# test1.net
KiCad netlist of a schematic drawn in EAGLE
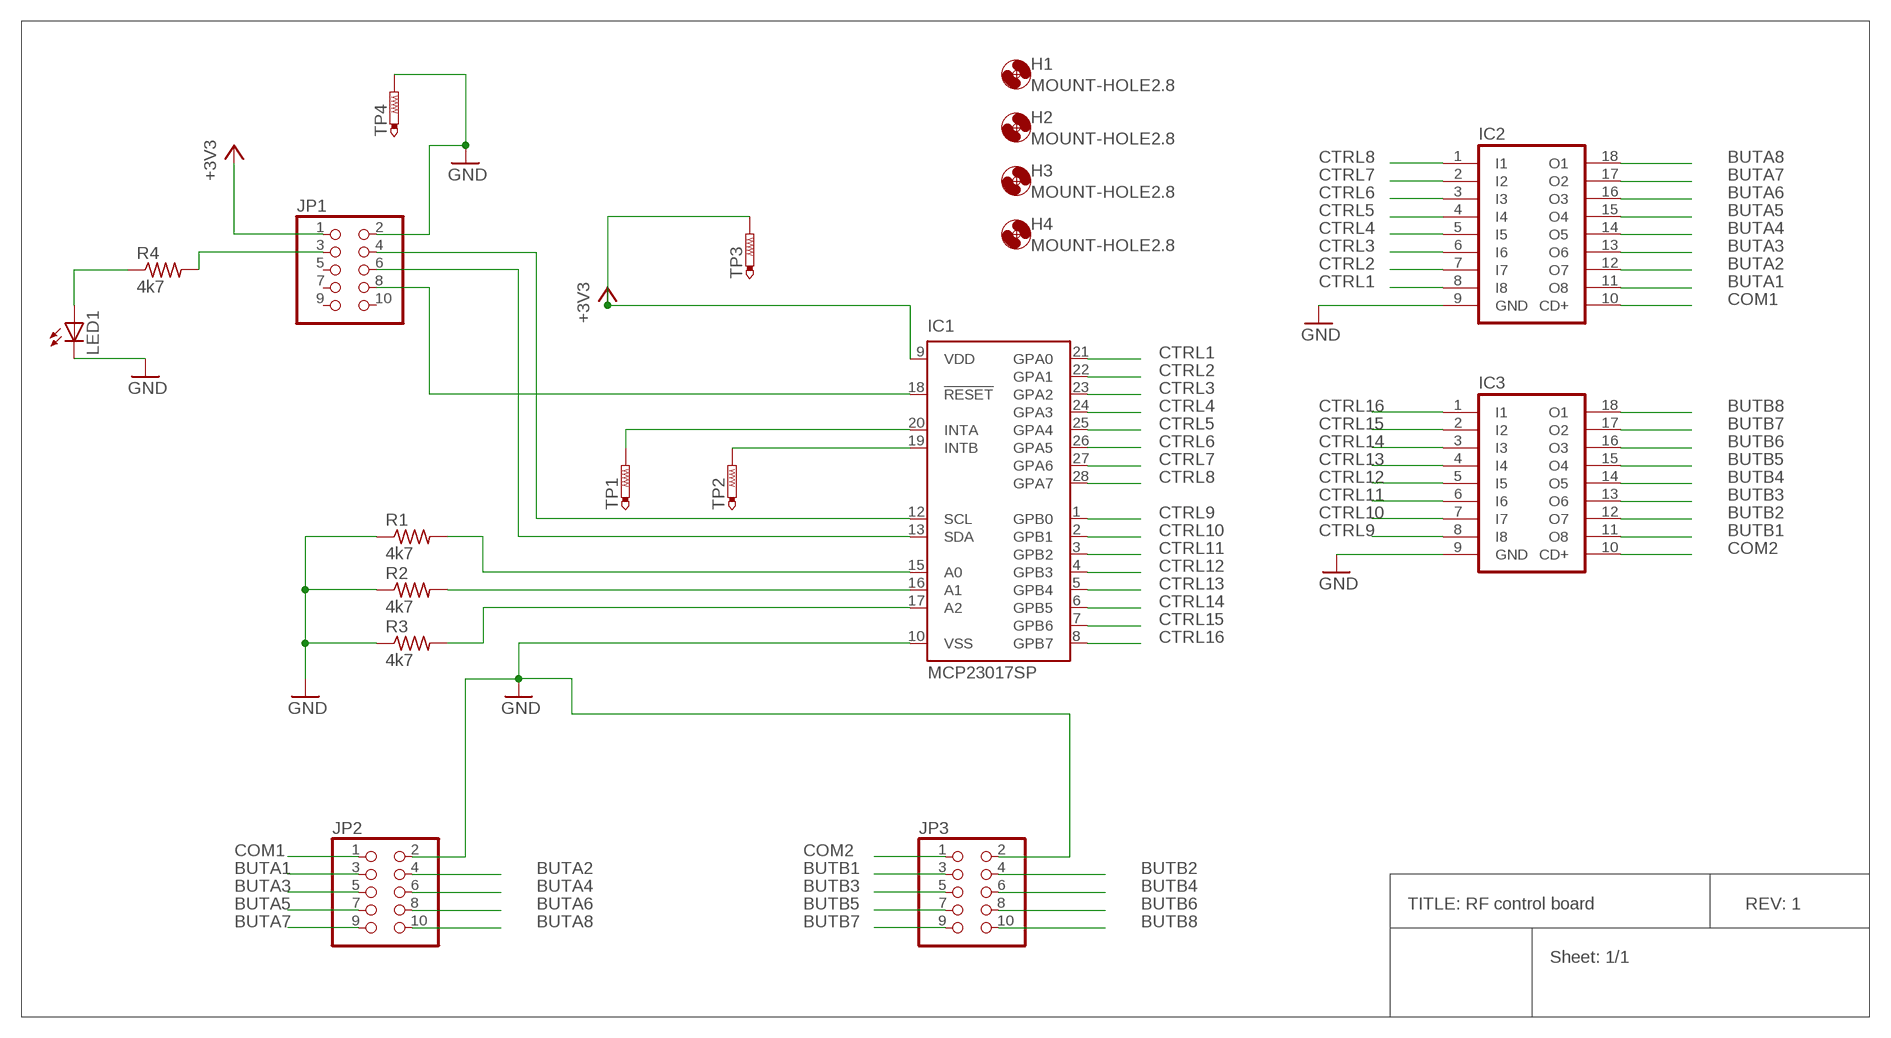
[diagram p0: schematic, sheet 1]

(export (version "E")
  (design (tool "Eeschema 10.0.6"))
  (components
    (comp (ref "H1")
      (value "MOUNT-HOLE2.8")
      (footprint "eagle-import:2,8")
      (libsource (lib "eagle-import") (part "MOUNT-HOLE2.8"))
    )
    (comp (ref "H2")
      (value "MOUNT-HOLE2.8")
      (footprint "eagle-import:2,8")
      (libsource (lib "eagle-import") (part "MOUNT-HOLE2.8"))
    )
    (comp (ref "H3")
      (value "MOUNT-HOLE2.8")
      (footprint "eagle-import:2,8")
      (libsource (lib "eagle-import") (part "MOUNT-HOLE2.8"))
    )
    (comp (ref "H4")
      (value "MOUNT-HOLE2.8")
      (footprint "eagle-import:2,8")
      (libsource (lib "eagle-import") (part "MOUNT-HOLE2.8"))
    )
    (comp (ref "IC1")
      (value "MCP23017SP")
      (footprint "eagle-import:DIL28-3")
      (libsource (lib "eagle-import") (part "MCP23017SP"))
    )
    (comp (ref "IC2")
      (value "ULN2803A")
      (footprint "eagle-import:DIL18")
      (libsource (lib "eagle-import") (part "ULN2803A"))
    )
    (comp (ref "IC3")
      (value "ULN2803A")
      (footprint "eagle-import:DIL18")
      (libsource (lib "eagle-import") (part "ULN2803A"))
    )
    (comp (ref "JP1")
      (value "PINHD-2X5")
      (footprint "eagle-import:2X05")
      (libsource (lib "eagle-import") (part "PINHD-2X5"))
    )
    (comp (ref "JP2")
      (value "PINHD-2X5")
      (footprint "eagle-import:2X05")
      (libsource (lib "eagle-import") (part "PINHD-2X5"))
    )
    (comp (ref "JP3")
      (value "PINHD-2X5")
      (footprint "eagle-import:2X05")
      (libsource (lib "eagle-import") (part "PINHD-2X5"))
    )
    (comp (ref "LED1")
      (value "LED5MM")
      (footprint "eagle-import:LED5MM")
      (libsource (lib "eagle-import") (part "LED5MM"))
    )
    (comp (ref "R1")
      (value "4k7")
      (footprint "eagle-import:0207_2V")
      (libsource (lib "eagle-import") (part "R-US_0207/2V"))
    )
    (comp (ref "R2")
      (value "4k7")
      (footprint "eagle-import:0207_2V")
      (libsource (lib "eagle-import") (part "R-US_0207/2V"))
    )
    (comp (ref "R3")
      (value "4k7")
      (footprint "eagle-import:0207_2V")
      (libsource (lib "eagle-import") (part "R-US_0207/2V"))
    )
    (comp (ref "R4")
      (value "4k7")
      (footprint "eagle-import:0207_2V")
      (libsource (lib "eagle-import") (part "R-US_0207/2V"))
    )
    (comp (ref "TP1")
      (value "PTR1B2,54")
      (footprint "eagle-import:B2,54")
      (libsource (lib "eagle-import") (part "PTR1B2,54"))
    )
    (comp (ref "TP2")
      (value "PTR1B2,54")
      (footprint "eagle-import:B2,54")
      (libsource (lib "eagle-import") (part "PTR1B2,54"))
    )
    (comp (ref "TP3")
      (value "PTR1B2,54")
      (footprint "eagle-import:B2,54")
      (libsource (lib "eagle-import") (part "PTR1B2,54"))
    )
    (comp (ref "TP4")
      (value "PTR1B2,54")
      (footprint "eagle-import:B2,54")
      (libsource (lib "eagle-import") (part "PTR1B2,54"))
    )
  )
  (nets
    (net (code "1") (name "+3V3") (class "Default")
      (node (ref "IC1") (pin "9") (pinfunction "VDD_9") (pintype "power_in"))
      (node (ref "JP1") (pin "1") (pinfunction "1_1") (pintype "passive"))
      (node (ref "TP3") (pin "TP") (pinfunction "TP_TP") (pintype "input"))
    )
    (net (code "2") (name "/BUTA1") (class "Default")
      (node (ref "IC2") (pin "11") (pinfunction "O8_11") (pintype "open_collector"))
      (node (ref "JP2") (pin "3") (pinfunction "3_3") (pintype "passive"))
    )
    (net (code "3") (name "/BUTA2") (class "Default")
      (node (ref "IC2") (pin "12") (pinfunction "O7_12") (pintype "open_collector"))
      (node (ref "JP2") (pin "4") (pinfunction "4_4") (pintype "passive"))
    )
    (net (code "4") (name "/BUTA3") (class "Default")
      (node (ref "IC2") (pin "13") (pinfunction "O6_13") (pintype "open_collector"))
      (node (ref "JP2") (pin "5") (pinfunction "5_5") (pintype "passive"))
    )
    (net (code "5") (name "/BUTA4") (class "Default")
      (node (ref "IC2") (pin "14") (pinfunction "O5_14") (pintype "open_collector"))
      (node (ref "JP2") (pin "6") (pinfunction "6_6") (pintype "passive"))
    )
    (net (code "6") (name "/BUTA5") (class "Default")
      (node (ref "IC2") (pin "15") (pinfunction "O4_15") (pintype "open_collector"))
      (node (ref "JP2") (pin "7") (pinfunction "7_7") (pintype "passive"))
    )
    (net (code "7") (name "/BUTA6") (class "Default")
      (node (ref "IC2") (pin "16") (pinfunction "O3_16") (pintype "open_collector"))
      (node (ref "JP2") (pin "8") (pinfunction "8_8") (pintype "passive"))
    )
    (net (code "8") (name "/BUTA7") (class "Default")
      (node (ref "IC2") (pin "17") (pinfunction "O2_17") (pintype "open_collector"))
      (node (ref "JP2") (pin "9") (pinfunction "9_9") (pintype "passive"))
    )
    (net (code "9") (name "/BUTA8") (class "Default")
      (node (ref "IC2") (pin "18") (pinfunction "O1_18") (pintype "open_collector"))
      (node (ref "JP2") (pin "10") (pinfunction "10_10") (pintype "passive"))
    )
    (net (code "10") (name "/BUTB1") (class "Default")
      (node (ref "IC3") (pin "11") (pinfunction "O8_11") (pintype "open_collector"))
      (node (ref "JP3") (pin "3") (pinfunction "3_3") (pintype "passive"))
    )
    (net (code "11") (name "/BUTB2") (class "Default")
      (node (ref "IC3") (pin "12") (pinfunction "O7_12") (pintype "open_collector"))
      (node (ref "JP3") (pin "4") (pinfunction "4_4") (pintype "passive"))
    )
    (net (code "12") (name "/BUTB3") (class "Default")
      (node (ref "IC3") (pin "13") (pinfunction "O6_13") (pintype "open_collector"))
      (node (ref "JP3") (pin "5") (pinfunction "5_5") (pintype "passive"))
    )
    (net (code "13") (name "/BUTB4") (class "Default")
      (node (ref "IC3") (pin "14") (pinfunction "O5_14") (pintype "open_collector"))
      (node (ref "JP3") (pin "6") (pinfunction "6_6") (pintype "passive"))
    )
    (net (code "14") (name "/BUTB5") (class "Default")
      (node (ref "IC3") (pin "15") (pinfunction "O4_15") (pintype "open_collector"))
      (node (ref "JP3") (pin "7") (pinfunction "7_7") (pintype "passive"))
    )
    (net (code "15") (name "/BUTB6") (class "Default")
      (node (ref "IC3") (pin "16") (pinfunction "O3_16") (pintype "open_collector"))
      (node (ref "JP3") (pin "8") (pinfunction "8_8") (pintype "passive"))
    )
    (net (code "16") (name "/BUTB7") (class "Default")
      (node (ref "IC3") (pin "17") (pinfunction "O2_17") (pintype "open_collector"))
      (node (ref "JP3") (pin "9") (pinfunction "9_9") (pintype "passive"))
    )
    (net (code "17") (name "/BUTB8") (class "Default")
      (node (ref "IC3") (pin "18") (pinfunction "O1_18") (pintype "open_collector"))
      (node (ref "JP3") (pin "10") (pinfunction "10_10") (pintype "passive"))
    )
    (net (code "18") (name "/COM1") (class "Default")
      (node (ref "IC2") (pin "10") (pinfunction "CD+_10") (pintype "passive"))
      (node (ref "JP2") (pin "1") (pinfunction "1_1") (pintype "passive"))
    )
    (net (code "19") (name "/COM2") (class "Default")
      (node (ref "IC3") (pin "10") (pinfunction "CD+_10") (pintype "passive"))
      (node (ref "JP3") (pin "1") (pinfunction "1_1") (pintype "passive"))
    )
    (net (code "20") (name "/CTRL1") (class "Default")
      (node (ref "IC1") (pin "21") (pinfunction "GPA0_21") (pintype "bidirectional"))
      (node (ref "IC2") (pin "8") (pinfunction "I8_8") (pintype "input"))
    )
    (net (code "21") (name "/CTRL2") (class "Default")
      (node (ref "IC1") (pin "22") (pinfunction "GPA1_22") (pintype "bidirectional"))
      (node (ref "IC2") (pin "7") (pinfunction "I7_7") (pintype "input"))
    )
    (net (code "22") (name "/CTRL3") (class "Default")
      (node (ref "IC1") (pin "23") (pinfunction "GPA2_23") (pintype "bidirectional"))
      (node (ref "IC2") (pin "6") (pinfunction "I6_6") (pintype "input"))
    )
    (net (code "23") (name "/CTRL4") (class "Default")
      (node (ref "IC1") (pin "24") (pinfunction "GPA3_24") (pintype "bidirectional"))
      (node (ref "IC2") (pin "5") (pinfunction "I5_5") (pintype "input"))
    )
    (net (code "24") (name "/CTRL5") (class "Default")
      (node (ref "IC1") (pin "25") (pinfunction "GPA4_25") (pintype "bidirectional"))
      (node (ref "IC2") (pin "4") (pinfunction "I4_4") (pintype "input"))
    )
    (net (code "25") (name "/CTRL6") (class "Default")
      (node (ref "IC1") (pin "26") (pinfunction "GPA5_26") (pintype "bidirectional"))
      (node (ref "IC2") (pin "3") (pinfunction "I3_3") (pintype "input"))
    )
    (net (code "26") (name "/CTRL7") (class "Default")
      (node (ref "IC1") (pin "27") (pinfunction "GPA6_27") (pintype "bidirectional"))
      (node (ref "IC2") (pin "2") (pinfunction "I2_2") (pintype "input"))
    )
    (net (code "27") (name "/CTRL8") (class "Default")
      (node (ref "IC1") (pin "28") (pinfunction "GPA7_28") (pintype "bidirectional"))
      (node (ref "IC2") (pin "1") (pinfunction "I1_1") (pintype "input"))
    )
    (net (code "28") (name "/CTRL9") (class "Default")
      (node (ref "IC1") (pin "1") (pinfunction "GPB0_1") (pintype "bidirectional"))
      (node (ref "IC3") (pin "8") (pinfunction "I8_8") (pintype "input"))
    )
    (net (code "29") (name "/CTRL10") (class "Default")
      (node (ref "IC1") (pin "2") (pinfunction "GPB1_2") (pintype "bidirectional"))
      (node (ref "IC3") (pin "7") (pinfunction "I7_7") (pintype "input"))
    )
    (net (code "30") (name "/CTRL11") (class "Default")
      (node (ref "IC1") (pin "3") (pinfunction "GPB2_3") (pintype "bidirectional"))
      (node (ref "IC3") (pin "6") (pinfunction "I6_6") (pintype "input"))
    )
    (net (code "31") (name "/CTRL12") (class "Default")
      (node (ref "IC1") (pin "4") (pinfunction "GPB3_4") (pintype "bidirectional"))
      (node (ref "IC3") (pin "5") (pinfunction "I5_5") (pintype "input"))
    )
    (net (code "32") (name "/CTRL13") (class "Default")
      (node (ref "IC1") (pin "5") (pinfunction "GPB4_5") (pintype "bidirectional"))
      (node (ref "IC3") (pin "4") (pinfunction "I4_4") (pintype "input"))
    )
    (net (code "33") (name "/CTRL14") (class "Default")
      (node (ref "IC1") (pin "6") (pinfunction "GPB5_6") (pintype "bidirectional"))
      (node (ref "IC3") (pin "3") (pinfunction "I3_3") (pintype "input"))
    )
    (net (code "34") (name "/CTRL15") (class "Default")
      (node (ref "IC1") (pin "7") (pinfunction "GPB6_7") (pintype "bidirectional"))
      (node (ref "IC3") (pin "2") (pinfunction "I2_2") (pintype "input"))
    )
    (net (code "35") (name "/CTRL16") (class "Default")
      (node (ref "IC1") (pin "8") (pinfunction "GPB7_8") (pintype "bidirectional"))
      (node (ref "IC3") (pin "1") (pinfunction "I1_1") (pintype "input"))
    )
    (net (code "36") (name "GND") (class "Default")
      (node (ref "IC1") (pin "10") (pinfunction "VSS_10") (pintype "power_in"))
      (node (ref "IC2") (pin "9") (pinfunction "GND_9") (pintype "power_in"))
      (node (ref "IC3") (pin "9") (pinfunction "GND_9") (pintype "power_in"))
      (node (ref "JP1") (pin "2") (pinfunction "2_2") (pintype "passive"))
      (node (ref "JP2") (pin "2") (pinfunction "2_2") (pintype "passive"))
      (node (ref "JP3") (pin "2") (pinfunction "2_2") (pintype "passive"))
      (node (ref "LED1") (pin "K") (pinfunction "C_K") (pintype "passive"))
      (node (ref "R1") (pin "1") (pinfunction "1_1") (pintype "passive"))
      (node (ref "R2") (pin "1") (pinfunction "1_1") (pintype "passive"))
      (node (ref "R3") (pin "1") (pinfunction "1_1") (pintype "passive"))
      (node (ref "TP4") (pin "TP") (pinfunction "TP_TP") (pintype "input"))
    )
    (net (code "37") (name "Net-(IC1-A0)") (class "Default")
      (node (ref "IC1") (pin "15") (pinfunction "A0_15") (pintype "input"))
      (node (ref "R1") (pin "2") (pinfunction "2_2") (pintype "passive"))
    )
    (net (code "38") (name "Net-(IC1-A1)") (class "Default")
      (node (ref "IC1") (pin "16") (pinfunction "A1_16") (pintype "input"))
      (node (ref "R2") (pin "2") (pinfunction "2_2") (pintype "passive"))
    )
    (net (code "39") (name "Net-(IC1-A2)") (class "Default")
      (node (ref "IC1") (pin "17") (pinfunction "A2_17") (pintype "input"))
      (node (ref "R3") (pin "2") (pinfunction "2_2") (pintype "passive"))
    )
    (net (code "40") (name "Net-(IC1-INTA)") (class "Default")
      (node (ref "IC1") (pin "20") (pinfunction "INTA_20") (pintype "output"))
      (node (ref "TP1") (pin "TP") (pinfunction "TP_TP") (pintype "input"))
    )
    (net (code "41") (name "Net-(IC1-INTB)") (class "Default")
      (node (ref "IC1") (pin "19") (pinfunction "INTB_19") (pintype "output"))
      (node (ref "TP2") (pin "TP") (pinfunction "TP_TP") (pintype "input"))
    )
    (net (code "42") (name "Net-(IC1-SCL)") (class "Default")
      (node (ref "IC1") (pin "12") (pinfunction "SCL_12") (pintype "input"))
      (node (ref "JP1") (pin "4") (pinfunction "4_4") (pintype "passive"))
    )
    (net (code "43") (name "Net-(IC1-SDA)") (class "Default")
      (node (ref "IC1") (pin "13") (pinfunction "SDA_13") (pintype "bidirectional"))
      (node (ref "JP1") (pin "6") (pinfunction "6_6") (pintype "passive"))
    )
    (net (code "44") (name "Net-(IC1-~{RESET})") (class "Default")
      (node (ref "IC1") (pin "18") (pinfunction "~{RESET}_18") (pintype "input"))
      (node (ref "JP1") (pin "8") (pinfunction "8_8") (pintype "passive"))
    )
    (net (code "45") (name "Net-(JP1-Pad3)") (class "Default")
      (node (ref "JP1") (pin "3") (pinfunction "3_3") (pintype "passive"))
      (node (ref "R4") (pin "2") (pinfunction "2_2") (pintype "passive"))
    )
    (net (code "46") (name "Net-(LED1-PadA)") (class "Default")
      (node (ref "LED1") (pin "A") (pinfunction "A_A") (pintype "passive"))
      (node (ref "R4") (pin "1") (pinfunction "1_1") (pintype "passive"))
    )
    (net (code "47") (name "unconnected-(JP1-Pad5)") (class "Default")
      (node (ref "JP1") (pin "5") (pinfunction "5_5") (pintype "passive"))
    )
    (net (code "48") (name "unconnected-(JP1-Pad7)") (class "Default")
      (node (ref "JP1") (pin "7") (pinfunction "7_7") (pintype "passive"))
    )
    (net (code "49") (name "unconnected-(JP1-Pad9)") (class "Default")
      (node (ref "JP1") (pin "9") (pinfunction "9_9") (pintype "passive"))
    )
    (net (code "50") (name "unconnected-(JP1-Pad10)") (class "Default")
      (node (ref "JP1") (pin "10") (pinfunction "10_10") (pintype "passive"))
    )
  )
)
